# switch.net
KiCad netlist of a schematic drawn in Altium Designer
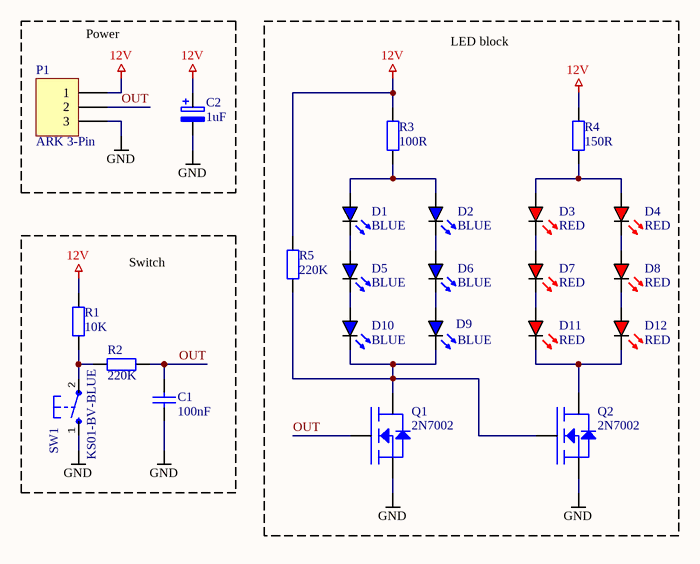
[diagram p0: switch.SchDoc]

(export (version "E")
  (design (tool "Eeschema 10.0.6"))
  (components
    (comp (ref "C1")
      (value "100nF")
      (footprint "C0805")
      (description "Capacitor")
      (libsource (lib "Library") (part "Cap"))
    )
    (comp (ref "C2")
      (value "1uF")
      (footprint "TANC_A")
      (description "Capacitor Polarized")
      (libsource (lib "Library") (part "Cap_Pol"))
    )
    (comp (ref "D1")
      (value "BLUE")
      (footprint "LED0805")
      (description "LED")
      (libsource (lib "Library") (part "LED_BLUE"))
    )
    (comp (ref "D2")
      (value "BLUE")
      (footprint "LED0805")
      (description "LED")
      (libsource (lib "Library") (part "LED_BLUE"))
    )
    (comp (ref "D3")
      (value "RED")
      (footprint "LED0805")
      (description "LED")
      (libsource (lib "Library") (part "LED_RED"))
    )
    (comp (ref "D4")
      (value "RED")
      (footprint "LED0805")
      (description "LED")
      (libsource (lib "Library") (part "LED_RED"))
    )
    (comp (ref "D5")
      (value "BLUE")
      (footprint "LED0805")
      (description "LED")
      (libsource (lib "Library") (part "LED_BLUE"))
    )
    (comp (ref "D6")
      (value "BLUE")
      (footprint "LED0805")
      (description "LED")
      (libsource (lib "Library") (part "LED_BLUE"))
    )
    (comp (ref "D7")
      (value "RED")
      (footprint "LED0805")
      (description "LED")
      (libsource (lib "Library") (part "LED_RED"))
    )
    (comp (ref "D8")
      (value "RED")
      (footprint "LED0805")
      (description "LED")
      (libsource (lib "Library") (part "LED_RED"))
    )
    (comp (ref "D9")
      (value "BLUE")
      (footprint "LED0805")
      (description "LED")
      (libsource (lib "Library") (part "LED_BLUE"))
    )
    (comp (ref "D10")
      (value "BLUE")
      (footprint "LED0805")
      (description "LED")
      (libsource (lib "Library") (part "LED_BLUE"))
    )
    (comp (ref "D11")
      (value "RED")
      (footprint "LED0805")
      (description "LED")
      (libsource (lib "Library") (part "LED_RED"))
    )
    (comp (ref "D12")
      (value "RED")
      (footprint "LED0805")
      (description "LED")
      (libsource (lib "Library") (part "LED_RED"))
    )
    (comp (ref "P1")
      (value "ARK 3-Pin")
      (footprint "ARK-3.5mm-3pin")
      (libsource (lib "Connectors") (part "ARK 3-Pin"))
    )
    (comp (ref "Q1")
      (value "2N7002")
      (footprint "SOT23")
      (description "N-MOSFET")
      (libsource (lib "Library") (part "2N7002(GSD)"))
    )
    (comp (ref "Q2")
      (value "2N7002")
      (footprint "SOT23")
      (description "N-MOSFET")
      (libsource (lib "Library") (part "2N7002(GSD)"))
    )
    (comp (ref "R1")
      (value "10K")
      (footprint "R0805")
      (description "Resistor")
      (libsource (lib "Library") (part "Res"))
    )
    (comp (ref "R2")
      (value "220K")
      (footprint "R0805")
      (description "Resistor")
      (libsource (lib "") (part "Res_1"))
    )
    (comp (ref "R3")
      (value "100R")
      (footprint "R0805")
      (description "Resistor")
      (libsource (lib "Library") (part "Res"))
    )
    (comp (ref "R4")
      (value "150R")
      (footprint "R0805")
      (description "Resistor")
      (libsource (lib "Library") (part "Res"))
    )
    (comp (ref "R5")
      (value "220K")
      (footprint "R0805")
      (description "Resistor")
      (libsource (lib "Library") (part "Res"))
    )
    (comp (ref "SW1")
      (value "KS01-BV-BLUE")
      (footprint "KS01-B")
      (description "Pozycje:2; SPST-NO; 0,01A/35VDC; 1,3N")
      (libsource (lib "Library") (part "KS01"))
    )
  )
  (nets
    (net (code "1") (name "/OUT") (class "Default")
      (node (ref "C1") (pin "1") (pinfunction "1_1") (pintype "passive"))
      (node (ref "P1") (pin "2") (pinfunction "2_2") (pintype "passive"))
      (node (ref "Q1") (pin "1") (pinfunction "G_1") (pintype "passive"))
      (node (ref "R2") (pin "2") (pinfunction "2_2") (pintype "passive"))
    )
    (net (code "2") (name "12V") (class "Default")
      (node (ref "C2") (pin "1") (pinfunction "1_1") (pintype "passive"))
      (node (ref "P1") (pin "1") (pinfunction "1_1") (pintype "passive"))
      (node (ref "R1") (pin "2") (pinfunction "2_2") (pintype "passive"))
      (node (ref "R3") (pin "2") (pinfunction "2_2") (pintype "passive"))
      (node (ref "R4") (pin "2") (pinfunction "2_2") (pintype "passive"))
      (node (ref "R5") (pin "2") (pinfunction "2_2") (pintype "passive"))
    )
    (net (code "3") (name "GND") (class "Default")
      (node (ref "C1") (pin "2") (pinfunction "2_2") (pintype "passive"))
      (node (ref "C2") (pin "2") (pinfunction "2_2") (pintype "passive"))
      (node (ref "P1") (pin "3") (pinfunction "3_3") (pintype "passive"))
      (node (ref "Q1") (pin "2") (pinfunction "S_2") (pintype "passive"))
      (node (ref "Q2") (pin "2") (pinfunction "S_2") (pintype "passive"))
      (node (ref "SW1") (pin "1") (pinfunction "S_1") (pintype "passive"))
    )
    (net (code "4") (name "Net-(D1-Pad1)") (class "Default")
      (node (ref "D1") (pin "1") (pinfunction "1_1") (pintype "passive"))
      (node (ref "D5") (pin "2") (pinfunction "2_2") (pintype "passive"))
    )
    (net (code "5") (name "Net-(D1-Pad2)") (class "Default")
      (node (ref "D1") (pin "2") (pinfunction "2_2") (pintype "passive"))
      (node (ref "D2") (pin "2") (pinfunction "2_2") (pintype "passive"))
      (node (ref "R3") (pin "1") (pinfunction "1_1") (pintype "passive"))
    )
    (net (code "6") (name "Net-(D2-Pad1)") (class "Default")
      (node (ref "D2") (pin "1") (pinfunction "1_1") (pintype "passive"))
      (node (ref "D6") (pin "2") (pinfunction "2_2") (pintype "passive"))
    )
    (net (code "7") (name "Net-(D3-Pad1)") (class "Default")
      (node (ref "D3") (pin "1") (pinfunction "1_1") (pintype "passive"))
      (node (ref "D7") (pin "2") (pinfunction "2_2") (pintype "passive"))
    )
    (net (code "8") (name "Net-(D3-Pad2)") (class "Default")
      (node (ref "D3") (pin "2") (pinfunction "2_2") (pintype "passive"))
      (node (ref "D4") (pin "2") (pinfunction "2_2") (pintype "passive"))
      (node (ref "R4") (pin "1") (pinfunction "1_1") (pintype "passive"))
    )
    (net (code "9") (name "Net-(D4-Pad1)") (class "Default")
      (node (ref "D4") (pin "1") (pinfunction "1_1") (pintype "passive"))
      (node (ref "D8") (pin "2") (pinfunction "2_2") (pintype "passive"))
    )
    (net (code "10") (name "Net-(D6-Pad1)") (class "Default")
      (node (ref "D6") (pin "1") (pinfunction "1_1") (pintype "passive"))
      (node (ref "D9") (pin "2") (pinfunction "2_2") (pintype "passive"))
    )
    (net (code "11") (name "Net-(D10-Pad2)") (class "Default")
      (node (ref "D10") (pin "2") (pinfunction "2_2") (pintype "passive"))
      (node (ref "D5") (pin "1") (pinfunction "1_1") (pintype "passive"))
    )
    (net (code "12") (name "Net-(D11-Pad2)") (class "Default")
      (node (ref "D11") (pin "2") (pinfunction "2_2") (pintype "passive"))
      (node (ref "D7") (pin "1") (pinfunction "1_1") (pintype "passive"))
    )
    (net (code "13") (name "Net-(D12-Pad2)") (class "Default")
      (node (ref "D12") (pin "2") (pinfunction "2_2") (pintype "passive"))
      (node (ref "D8") (pin "1") (pinfunction "1_1") (pintype "passive"))
    )
    (net (code "14") (name "Net-(Q1-D)") (class "Default")
      (node (ref "D10") (pin "1") (pinfunction "1_1") (pintype "passive"))
      (node (ref "D9") (pin "1") (pinfunction "1_1") (pintype "passive"))
      (node (ref "Q1") (pin "3") (pinfunction "D_3") (pintype "passive"))
      (node (ref "Q2") (pin "1") (pinfunction "G_1") (pintype "passive"))
      (node (ref "R5") (pin "1") (pinfunction "1_1") (pintype "passive"))
    )
    (net (code "15") (name "Net-(Q2-D)") (class "Default")
      (node (ref "D11") (pin "1") (pinfunction "1_1") (pintype "passive"))
      (node (ref "D12") (pin "1") (pinfunction "1_1") (pintype "passive"))
      (node (ref "Q2") (pin "3") (pinfunction "D_3") (pintype "passive"))
    )
    (net (code "16") (name "Net-(SW1-P)") (class "Default")
      (node (ref "R1") (pin "1") (pinfunction "1_1") (pintype "passive"))
      (node (ref "R2") (pin "1") (pinfunction "1_1") (pintype "passive"))
      (node (ref "SW1") (pin "2") (pinfunction "P_2") (pintype "passive"))
    )
  )
)
